# SoC_DDR.net
KiCad netlist of a schematic drawn in Altium Designer
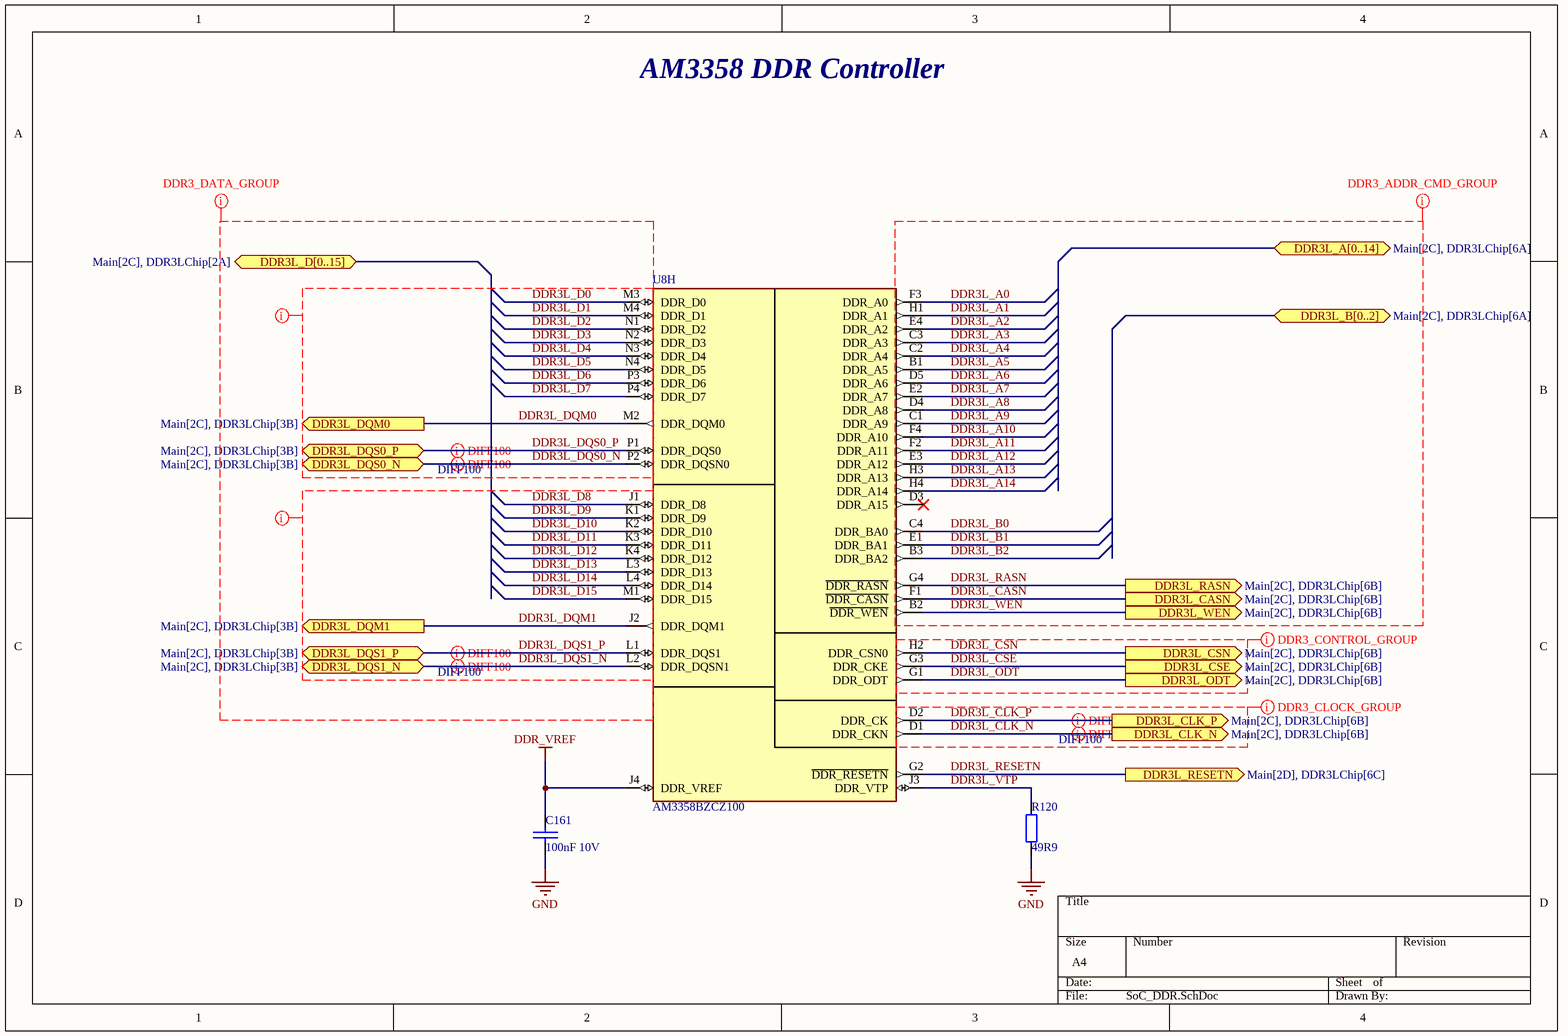
[diagram p0: SoC_DDR.SchDoc]

(export (version "E")
  (design (tool "Eeschema 10.0.6"))
  (components
    (comp (ref "C161")
      (value "100nF 10V")
      (footprint "C_0201")
      (description "Capacitor 0201 SMD")
      (libsource (lib "tor1kkLib") (part "C_0201"))
    )
    (comp (ref "R120")
      (value "49R9")
      (footprint "R_0402")
      (description "Resistor 0402 SMD")
      (libsource (lib "tor1kkLib") (part "R_0402"))
    )
    (comp (ref "U8")
      (value "AM3358BZCZ100")
      (footprint "BGA324C80P18X18_1500X1500X140")
      (description "ARM-ASeries 1GHz NFBGA-324 Microcontrollers (MCU/MPU/SOC) ROHS")
      (fields (field (name "MANUFACTURER") "Texas Instruments"))
      (libsource (lib "tor1kkLib") (part "AM3358BZCZ100"))
    )
  )
  (nets
    (net (code "1") (name "/DDR3L_A0") (class "Default")
      (node (ref "U8") (pin "F3") (pinfunction "DDR_A0_F3") (pintype "output"))
    )
    (net (code "2") (name "/DDR3L_A1") (class "Default")
      (node (ref "U8") (pin "H1") (pinfunction "DDR_A1_H1") (pintype "output"))
    )
    (net (code "3") (name "/DDR3L_A2") (class "Default")
      (node (ref "U8") (pin "E4") (pinfunction "DDR_A2_E4") (pintype "output"))
    )
    (net (code "4") (name "/DDR3L_A3") (class "Default")
      (node (ref "U8") (pin "C3") (pinfunction "DDR_A3_C3") (pintype "output"))
    )
    (net (code "5") (name "/DDR3L_A4") (class "Default")
      (node (ref "U8") (pin "C2") (pinfunction "DDR_A4_C2") (pintype "output"))
    )
    (net (code "6") (name "/DDR3L_A5") (class "Default")
      (node (ref "U8") (pin "B1") (pinfunction "DDR_A5_B1") (pintype "output"))
    )
    (net (code "7") (name "/DDR3L_A6") (class "Default")
      (node (ref "U8") (pin "D5") (pinfunction "DDR_A6_D5") (pintype "output"))
    )
    (net (code "8") (name "/DDR3L_A7") (class "Default")
      (node (ref "U8") (pin "E2") (pinfunction "DDR_A7_E2") (pintype "output"))
    )
    (net (code "9") (name "/DDR3L_A8") (class "Default")
      (node (ref "U8") (pin "D4") (pinfunction "DDR_A8_D4") (pintype "output"))
    )
    (net (code "10") (name "/DDR3L_A9") (class "Default")
      (node (ref "U8") (pin "C1") (pinfunction "DDR_A9_C1") (pintype "output"))
    )
    (net (code "11") (name "/DDR3L_A10") (class "Default")
      (node (ref "U8") (pin "F4") (pinfunction "DDR_A10_F4") (pintype "output"))
    )
    (net (code "12") (name "/DDR3L_A11") (class "Default")
      (node (ref "U8") (pin "F2") (pinfunction "DDR_A11_F2") (pintype "output"))
    )
    (net (code "13") (name "/DDR3L_A12") (class "Default")
      (node (ref "U8") (pin "E3") (pinfunction "DDR_A12_E3") (pintype "output"))
    )
    (net (code "14") (name "/DDR3L_A13") (class "Default")
      (node (ref "U8") (pin "H3") (pinfunction "DDR_A13_H3") (pintype "output"))
    )
    (net (code "15") (name "/DDR3L_A14") (class "Default")
      (node (ref "U8") (pin "H4") (pinfunction "DDR_A14_H4") (pintype "output"))
    )
    (net (code "17") (name "/DDR3L_B0") (class "Default")
      (node (ref "U8") (pin "C4") (pinfunction "DDR_BA0_C4") (pintype "output"))
    )
    (net (code "18") (name "/DDR3L_B1") (class "Default")
      (node (ref "U8") (pin "E1") (pinfunction "DDR_BA1_E1") (pintype "output"))
    )
    (net (code "19") (name "/DDR3L_B2") (class "Default")
      (node (ref "U8") (pin "B3") (pinfunction "DDR_BA2_B3") (pintype "output"))
    )
    (net (code "21") (name "/DDR3L_CASN") (class "Default")
      (node (ref "U8") (pin "F1") (pinfunction "~{DDR_CASN}_F1") (pintype "output"))
    )
    (net (code "22") (name "/DDR3L_CLK_N") (class "Default")
      (node (ref "U8") (pin "D1") (pinfunction "DDR_CKN_D1") (pintype "output"))
    )
    (net (code "23") (name "/DDR3L_CLK_P") (class "Default")
      (node (ref "U8") (pin "D2") (pinfunction "DDR_CK_D2") (pintype "output"))
    )
    (net (code "24") (name "/DDR3L_CSE") (class "Default")
      (node (ref "U8") (pin "G3") (pinfunction "DDR_CKE_G3") (pintype "output"))
    )
    (net (code "25") (name "/DDR3L_CSN") (class "Default")
      (node (ref "U8") (pin "H2") (pinfunction "DDR_CSN0_H2") (pintype "output"))
    )
    (net (code "26") (name "/DDR3L_D0") (class "Default")
      (node (ref "U8") (pin "M3") (pinfunction "DDR_D0_M3") (pintype "bidirectional"))
    )
    (net (code "27") (name "/DDR3L_D1") (class "Default")
      (node (ref "U8") (pin "M4") (pinfunction "DDR_D1_M4") (pintype "bidirectional"))
    )
    (net (code "28") (name "/DDR3L_D2") (class "Default")
      (node (ref "U8") (pin "N1") (pinfunction "DDR_D2_N1") (pintype "bidirectional"))
    )
    (net (code "29") (name "/DDR3L_D3") (class "Default")
      (node (ref "U8") (pin "N2") (pinfunction "DDR_D3_N2") (pintype "bidirectional"))
    )
    (net (code "30") (name "/DDR3L_D4") (class "Default")
      (node (ref "U8") (pin "N3") (pinfunction "DDR_D4_N3") (pintype "bidirectional"))
    )
    (net (code "31") (name "/DDR3L_D5") (class "Default")
      (node (ref "U8") (pin "N4") (pinfunction "DDR_D5_N4") (pintype "bidirectional"))
    )
    (net (code "32") (name "/DDR3L_D6") (class "Default")
      (node (ref "U8") (pin "P3") (pinfunction "DDR_D6_P3") (pintype "bidirectional"))
    )
    (net (code "33") (name "/DDR3L_D7") (class "Default")
      (node (ref "U8") (pin "P4") (pinfunction "DDR_D7_P4") (pintype "bidirectional"))
    )
    (net (code "34") (name "/DDR3L_D8") (class "Default")
      (node (ref "U8") (pin "J1") (pinfunction "DDR_D8_J1") (pintype "bidirectional"))
    )
    (net (code "35") (name "/DDR3L_D9") (class "Default")
      (node (ref "U8") (pin "K1") (pinfunction "DDR_D9_K1") (pintype "bidirectional"))
    )
    (net (code "36") (name "/DDR3L_D10") (class "Default")
      (node (ref "U8") (pin "K2") (pinfunction "DDR_D10_K2") (pintype "bidirectional"))
    )
    (net (code "37") (name "/DDR3L_D11") (class "Default")
      (node (ref "U8") (pin "K3") (pinfunction "DDR_D11_K3") (pintype "bidirectional"))
    )
    (net (code "38") (name "/DDR3L_D12") (class "Default")
      (node (ref "U8") (pin "K4") (pinfunction "DDR_D12_K4") (pintype "bidirectional"))
    )
    (net (code "39") (name "/DDR3L_D13") (class "Default")
      (node (ref "U8") (pin "L3") (pinfunction "DDR_D13_L3") (pintype "bidirectional"))
    )
    (net (code "40") (name "/DDR3L_D14") (class "Default")
      (node (ref "U8") (pin "L4") (pinfunction "DDR_D14_L4") (pintype "bidirectional"))
    )
    (net (code "41") (name "/DDR3L_D15") (class "Default")
      (node (ref "U8") (pin "M1") (pinfunction "DDR_D15_M1") (pintype "bidirectional"))
    )
    (net (code "42") (name "/DDR3L_DQM0") (class "Default")
      (node (ref "U8") (pin "M2") (pinfunction "DDR_DQM0_M2") (pintype "output"))
    )
    (net (code "43") (name "/DDR3L_DQM1") (class "Default")
      (node (ref "U8") (pin "J2") (pinfunction "DDR_DQM1_J2") (pintype "output"))
    )
    (net (code "44") (name "/DDR3L_DQS0_N") (class "Default")
      (node (ref "U8") (pin "P2") (pinfunction "DDR_DQSN0_P2") (pintype "bidirectional"))
    )
    (net (code "45") (name "/DDR3L_DQS0_P") (class "Default")
      (node (ref "U8") (pin "P1") (pinfunction "DDR_DQS0_P1") (pintype "bidirectional"))
    )
    (net (code "46") (name "/DDR3L_DQS1_N") (class "Default")
      (node (ref "U8") (pin "L2") (pinfunction "DDR_DQSN1_L2") (pintype "bidirectional"))
    )
    (net (code "47") (name "/DDR3L_DQS1_P") (class "Default")
      (node (ref "U8") (pin "L1") (pinfunction "DDR_DQS1_L1") (pintype "bidirectional"))
    )
    (net (code "49") (name "/DDR3L_ODT") (class "Default")
      (node (ref "U8") (pin "G1") (pinfunction "DDR_ODT_G1") (pintype "output"))
    )
    (net (code "50") (name "/DDR3L_RASN") (class "Default")
      (node (ref "U8") (pin "G4") (pinfunction "~{DDR_RASN}_G4") (pintype "output"))
    )
    (net (code "51") (name "/DDR3L_RESETN") (class "Default")
      (node (ref "U8") (pin "G2") (pinfunction "~{DDR_RESETN}_G2") (pintype "output"))
    )
    (net (code "52") (name "/DDR3L_VTP") (class "Default")
      (node (ref "R120") (pin "2") (pintype "passive"))
      (node (ref "U8") (pin "J3") (pinfunction "DDR_VTP_J3") (pintype "bidirectional"))
    )
    (net (code "53") (name "/DDR3L_WEN") (class "Default")
      (node (ref "U8") (pin "B2") (pinfunction "~{DDR_WEN}_B2") (pintype "output"))
    )
    (net (code "54") (name "DDR_VREF") (class "Default")
      (node (ref "C161") (pin "1") (pintype "passive"))
      (node (ref "U8") (pin "J4") (pinfunction "DDR_VREF_J4") (pintype "bidirectional"))
    )
    (net (code "55") (name "GND") (class "Default")
      (node (ref "C161") (pin "2") (pintype "passive"))
      (node (ref "R120") (pin "1") (pintype "passive"))
    )
    (net (code "56") (name "unconnected-(U8H-DDR_A15-PadD3)") (class "Default")
      (node (ref "U8") (pin "D3") (pinfunction "DDR_A15_D3") (pintype "output+no_connect"))
    )
  )
)
